# monarchdtv.net
KiCad netlist of a schematic drawn in EAGLE
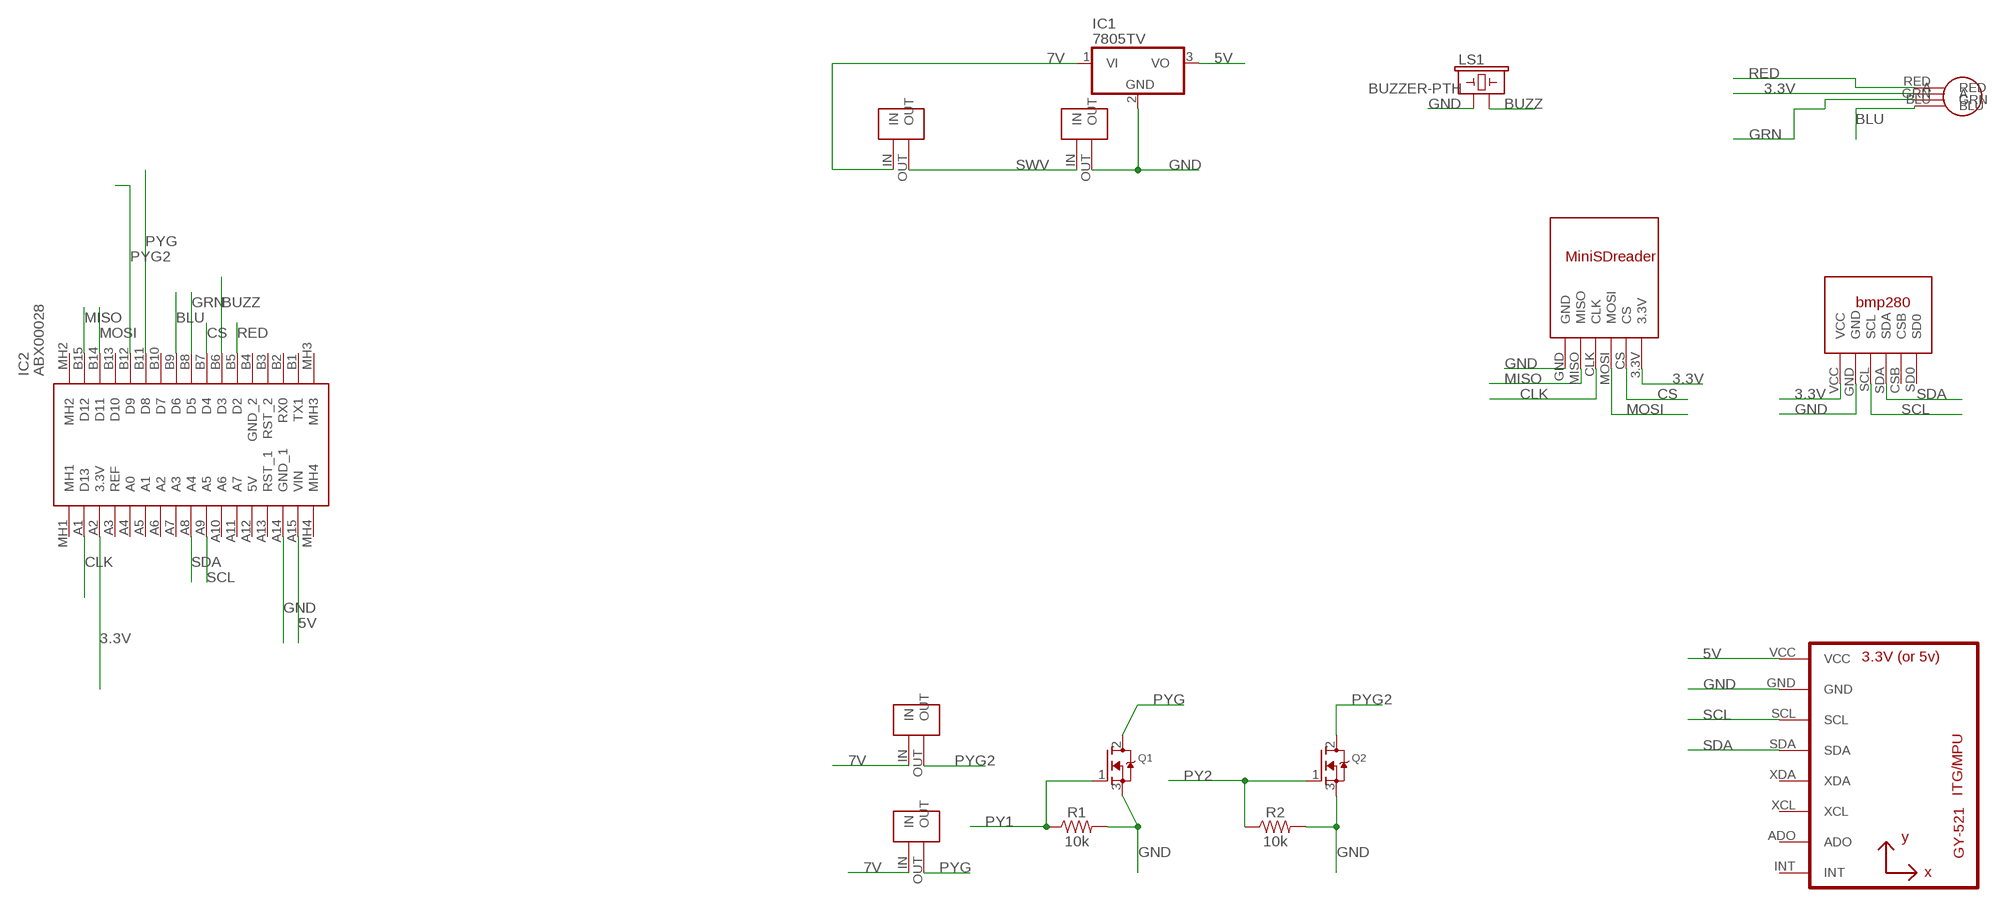
[diagram p0: schematic, sheet 1]

(export (version "E")
  (design (tool "Eeschema 10.0.6"))
  (components
    (comp (ref "IC1")
      (value "7805TV")
      (footprint "eagle-import:TO220V")
      (libsource (lib "eagle-import") (part "78TV05"))
    )
    (comp (ref "IC2")
      (value "ABX00028")
      (footprint "eagle-import:ABX00028")
      (fields (field (name "MOUSER_PART_NUMBER") "782-ABX00028"))
      (libsource (lib "eagle-import") (part "ABX00028"))
    )
    (comp (ref "LS1")
      (value "BUZZER-PTH")
      (footprint "eagle-import:BUZZER-12MM")
      (libsource (lib "eagle-import") (part "BUZZER-PTH"))
    )
    (comp (ref "Q1")
      (value "MOSFET-NGDS_TO220V")
      (footprint "eagle-import:TO220V")
      (libsource (lib "eagle-import") (part "MOSFET-NGDS_TO220V"))
    )
    (comp (ref "Q2")
      (value "MOSFET-NGDS_TO220V")
      (footprint "eagle-import:TO220V")
      (libsource (lib "eagle-import") (part "MOSFET-NGDS_TO220V"))
    )
    (comp (ref "R1")
      (value "10k")
      (footprint "eagle-import:AXIAL-0.1-KIT")
      (libsource (lib "eagle-import") (part "10KOHM-VERT_KIT-1/6W-5%"))
    )
    (comp (ref "R2")
      (value "10k")
      (footprint "eagle-import:AXIAL-0.1-KIT")
      (libsource (lib "eagle-import") (part "10KOHM-VERT_KIT-1/6W-5%"))
    )
    (comp (ref "U$2")
      (value "BMP280")
      (footprint "eagle-import:BMP280")
      (libsource (lib "eagle-import") (part "BMP280"))
    )
    (comp (ref "U$3")
      (value "MINISDREADER")
      (footprint "eagle-import:MINISDREADER")
      (libsource (lib "eagle-import") (part "MINISDREADER"))
    )
    (comp (ref "U$4")
      (value "SWITCH")
      (footprint "eagle-import:SWITCH")
      (libsource (lib "eagle-import") (part "SWITCH"))
    )
    (comp (ref "U$5")
      (value "SWITCH")
      (footprint "eagle-import:SWITCH")
      (libsource (lib "eagle-import") (part "SWITCH"))
    )
    (comp (ref "U$6")
      (value "SWITCH")
      (footprint "eagle-import:SWITCH")
      (libsource (lib "eagle-import") (part "SWITCH"))
    )
    (comp (ref "U$7")
      (value "SWITCH")
      (footprint "eagle-import:SWITCH")
      (libsource (lib "eagle-import") (part "SWITCH"))
    )
    (comp (ref "U$9")
      (value "LED")
      (footprint "eagle-import:LED")
      (libsource (lib "eagle-import") (part "LED"))
    )
    (comp (ref "U1")
      (value "GY-521MPU6050")
      (footprint "eagle-import:GY-521")
      (libsource (lib "eagle-import") (part "GY-521MPU6050"))
    )
  )
  (nets
    (net (code "1") (name "/3.3V") (class "Default")
      (node (ref "IC2") (pin "A2") (pinfunction "3.3V_A2") (pintype "bidirectional"))
      (node (ref "U$2") (pin "VCC") (pinfunction "VCC_VCC") (pintype "bidirectional"))
      (node (ref "U$3") (pin "3.3V") (pinfunction "3.3V_3.3V") (pintype "bidirectional"))
      (node (ref "U$9") (pin "A") (pinfunction "A_A") (pintype "bidirectional"))
    )
    (net (code "2") (name "/5V") (class "Default")
      (node (ref "IC1") (pin "3") (pinfunction "VO_3") (pintype "passive"))
      (node (ref "IC2") (pin "A15") (pinfunction "VIN_A15") (pintype "bidirectional"))
      (node (ref "U1") (pin "VCC") (pinfunction "VCC_VCC") (pintype "bidirectional"))
    )
    (net (code "3") (name "/7V") (class "Default")
      (node (ref "IC1") (pin "1") (pinfunction "VI_1") (pintype "input"))
      (node (ref "U$5") (pin "IN") (pinfunction "IN_IN") (pintype "bidirectional"))
      (node (ref "U$6") (pin "IN") (pinfunction "IN_IN") (pintype "bidirectional"))
      (node (ref "U$7") (pin "IN") (pinfunction "IN_IN") (pintype "bidirectional"))
    )
    (net (code "4") (name "/BLU") (class "Default")
      (node (ref "IC2") (pin "B9") (pinfunction "D6_B9") (pintype "bidirectional"))
      (node (ref "U$9") (pin "BLU") (pinfunction "BLU_BLU") (pintype "bidirectional"))
    )
    (net (code "5") (name "/BUZZ") (class "Default")
      (node (ref "IC2") (pin "B6") (pinfunction "D3_B6") (pintype "bidirectional"))
      (node (ref "LS1") (pin "-") (pinfunction "2_-") (pintype "passive"))
    )
    (net (code "6") (name "/CLK") (class "Default")
      (node (ref "IC2") (pin "A1") (pinfunction "D13_A1") (pintype "bidirectional"))
      (node (ref "U$3") (pin "CLK") (pinfunction "CLK_CLK") (pintype "bidirectional"))
    )
    (net (code "7") (name "/CS") (class "Default")
      (node (ref "IC2") (pin "B7") (pinfunction "D4_B7") (pintype "bidirectional"))
      (node (ref "U$3") (pin "CS") (pinfunction "CS_CS") (pintype "bidirectional"))
    )
    (net (code "8") (name "/GND") (class "Default")
      (node (ref "IC1") (pin "2") (pinfunction "GND_2") (pintype "passive"))
      (node (ref "IC2") (pin "A14") (pinfunction "GND_1_A14") (pintype "bidirectional"))
      (node (ref "LS1") (pin "+") (pinfunction "1_+") (pintype "passive"))
      (node (ref "Q1") (pin "3") (pinfunction "S_3") (pintype "bidirectional"))
      (node (ref "Q2") (pin "3") (pinfunction "S_3") (pintype "bidirectional"))
      (node (ref "R1") (pin "P$2") (pinfunction "2_P$2") (pintype "passive"))
      (node (ref "R2") (pin "P$2") (pinfunction "2_P$2") (pintype "passive"))
      (node (ref "U$2") (pin "GND") (pinfunction "GND_GND") (pintype "bidirectional"))
      (node (ref "U$3") (pin "GND") (pinfunction "GND_GND") (pintype "bidirectional"))
      (node (ref "U$4") (pin "OUT") (pinfunction "OUT_OUT") (pintype "bidirectional"))
      (node (ref "U1") (pin "GND") (pinfunction "GND_GND") (pintype "bidirectional"))
    )
    (net (code "9") (name "/GRN") (class "Default")
      (node (ref "IC2") (pin "B8") (pinfunction "D5_B8") (pintype "bidirectional"))
      (node (ref "U$9") (pin "GRN") (pinfunction "GRN_GRN") (pintype "bidirectional"))
    )
    (net (code "10") (name "/MISO") (class "Default")
      (node (ref "IC2") (pin "B15") (pinfunction "D12_B15") (pintype "bidirectional"))
      (node (ref "U$3") (pin "MISO") (pinfunction "MISO_MISO") (pintype "bidirectional"))
    )
    (net (code "11") (name "/MOSI") (class "Default")
      (node (ref "IC2") (pin "B14") (pinfunction "D11_B14") (pintype "bidirectional"))
      (node (ref "U$3") (pin "MOSI") (pinfunction "MOSI_MOSI") (pintype "bidirectional"))
    )
    (net (code "12") (name "/PY1") (class "Default")
      (node (ref "Q1") (pin "1") (pinfunction "G_1") (pintype "bidirectional"))
      (node (ref "R1") (pin "P$1") (pinfunction "1_P$1") (pintype "passive"))
    )
    (net (code "13") (name "/PY2") (class "Default")
      (node (ref "Q2") (pin "1") (pinfunction "G_1") (pintype "bidirectional"))
      (node (ref "R2") (pin "P$1") (pinfunction "1_P$1") (pintype "passive"))
    )
    (net (code "14") (name "/PYG") (class "Default")
      (node (ref "IC2") (pin "B11") (pinfunction "D8_B11") (pintype "bidirectional"))
      (node (ref "Q1") (pin "2") (pinfunction "D_2") (pintype "bidirectional"))
      (node (ref "U$6") (pin "OUT") (pinfunction "OUT_OUT") (pintype "bidirectional"))
    )
    (net (code "15") (name "/PYG2") (class "Default")
      (node (ref "IC2") (pin "B12") (pinfunction "D9_B12") (pintype "bidirectional"))
      (node (ref "Q2") (pin "2") (pinfunction "D_2") (pintype "bidirectional"))
      (node (ref "U$5") (pin "OUT") (pinfunction "OUT_OUT") (pintype "bidirectional"))
    )
    (net (code "16") (name "/RED") (class "Default")
      (node (ref "IC2") (pin "B5") (pinfunction "D2_B5") (pintype "bidirectional"))
      (node (ref "U$9") (pin "RED") (pinfunction "RED_RED") (pintype "bidirectional"))
    )
    (net (code "17") (name "/SCL") (class "Default")
      (node (ref "IC2") (pin "A9") (pinfunction "A5_A9") (pintype "bidirectional"))
      (node (ref "U$2") (pin "SCL") (pinfunction "SCL_SCL") (pintype "bidirectional"))
      (node (ref "U1") (pin "SCL") (pinfunction "SCL_SCL") (pintype "bidirectional"))
    )
    (net (code "18") (name "/SDA") (class "Default")
      (node (ref "IC2") (pin "A8") (pinfunction "A4_A8") (pintype "bidirectional"))
      (node (ref "U$2") (pin "SDA") (pinfunction "SDA_SDA") (pintype "bidirectional"))
      (node (ref "U1") (pin "SDA") (pinfunction "SDA_SDA") (pintype "bidirectional"))
    )
    (net (code "19") (name "/SWV") (class "Default")
      (node (ref "U$4") (pin "IN") (pinfunction "IN_IN") (pintype "bidirectional"))
      (node (ref "U$7") (pin "OUT") (pinfunction "OUT_OUT") (pintype "bidirectional"))
    )
    (net (code "20") (name "unconnected-(IC2-5V-PadA12)") (class "Default")
      (node (ref "IC2") (pin "A12") (pinfunction "5V_A12") (pintype "bidirectional"))
    )
    (net (code "21") (name "unconnected-(IC2-A0-PadA4)") (class "Default")
      (node (ref "IC2") (pin "A4") (pinfunction "A0_A4") (pintype "bidirectional"))
    )
    (net (code "22") (name "unconnected-(IC2-A1-PadA5)") (class "Default")
      (node (ref "IC2") (pin "A5") (pinfunction "A1_A5") (pintype "bidirectional"))
    )
    (net (code "23") (name "unconnected-(IC2-A2-PadA6)") (class "Default")
      (node (ref "IC2") (pin "A6") (pinfunction "A2_A6") (pintype "bidirectional"))
    )
    (net (code "24") (name "unconnected-(IC2-A3-PadA7)") (class "Default")
      (node (ref "IC2") (pin "A7") (pinfunction "A3_A7") (pintype "bidirectional"))
    )
    (net (code "25") (name "unconnected-(IC2-A6-PadA10)") (class "Default")
      (node (ref "IC2") (pin "A10") (pinfunction "A6_A10") (pintype "bidirectional"))
    )
    (net (code "26") (name "unconnected-(IC2-A7-PadA11)") (class "Default")
      (node (ref "IC2") (pin "A11") (pinfunction "A7_A11") (pintype "bidirectional"))
    )
    (net (code "27") (name "unconnected-(IC2-D7-PadB10)") (class "Default")
      (node (ref "IC2") (pin "B10") (pinfunction "D7_B10") (pintype "bidirectional"))
    )
    (net (code "28") (name "unconnected-(IC2-D10-PadB13)") (class "Default")
      (node (ref "IC2") (pin "B13") (pinfunction "D10_B13") (pintype "bidirectional"))
    )
    (net (code "29") (name "unconnected-(IC2-GND_2-PadB4)") (class "Default")
      (node (ref "IC2") (pin "B4") (pinfunction "GND_2_B4") (pintype "bidirectional"))
    )
    (net (code "30") (name "unconnected-(IC2-PadMH1)") (class "Default")
      (node (ref "IC2") (pin "MH1") (pinfunction "MH1_MH1") (pintype "bidirectional"))
    )
    (net (code "31") (name "unconnected-(IC2-PadMH2)") (class "Default")
      (node (ref "IC2") (pin "MH2") (pinfunction "MH2_MH2") (pintype "bidirectional"))
    )
    (net (code "32") (name "unconnected-(IC2-PadMH3)") (class "Default")
      (node (ref "IC2") (pin "MH3") (pinfunction "MH3_MH3") (pintype "bidirectional"))
    )
    (net (code "33") (name "unconnected-(IC2-PadMH4)") (class "Default")
      (node (ref "IC2") (pin "MH4") (pinfunction "MH4_MH4") (pintype "bidirectional"))
    )
    (net (code "34") (name "unconnected-(IC2-REF-PadA3)") (class "Default")
      (node (ref "IC2") (pin "A3") (pinfunction "REF_A3") (pintype "bidirectional"))
    )
    (net (code "35") (name "unconnected-(IC2-RST_1-PadA13)") (class "Default")
      (node (ref "IC2") (pin "A13") (pinfunction "RST_1_A13") (pintype "bidirectional"))
    )
    (net (code "36") (name "unconnected-(IC2-RST_2-PadB3)") (class "Default")
      (node (ref "IC2") (pin "B3") (pinfunction "RST_2_B3") (pintype "bidirectional"))
    )
    (net (code "37") (name "unconnected-(IC2-RX0-PadB2)") (class "Default")
      (node (ref "IC2") (pin "B2") (pinfunction "RX0_B2") (pintype "bidirectional"))
    )
    (net (code "38") (name "unconnected-(IC2-TX1-PadB1)") (class "Default")
      (node (ref "IC2") (pin "B1") (pinfunction "TX1_B1") (pintype "bidirectional"))
    )
    (net (code "39") (name "unconnected-(U$2-PadCSB)") (class "Default")
      (node (ref "U$2") (pin "CSB") (pinfunction "CSB_CSB") (pintype "bidirectional"))
    )
    (net (code "40") (name "unconnected-(U$2-PadSD0)") (class "Default")
      (node (ref "U$2") (pin "SD0") (pinfunction "SD0_SD0") (pintype "bidirectional"))
    )
    (net (code "41") (name "unconnected-(U1-PadADO)") (class "Default")
      (node (ref "U1") (pin "ADO") (pinfunction "ADO_ADO") (pintype "bidirectional"))
    )
    (net (code "42") (name "unconnected-(U1-PadINT)") (class "Default")
      (node (ref "U1") (pin "INT") (pinfunction "INT_INT") (pintype "bidirectional"))
    )
    (net (code "43") (name "unconnected-(U1-PadXCL)") (class "Default")
      (node (ref "U1") (pin "XCL") (pinfunction "XCL_XCL") (pintype "bidirectional"))
    )
    (net (code "44") (name "unconnected-(U1-PadXDA)") (class "Default")
      (node (ref "U1") (pin "XDA") (pinfunction "XDA_XDA") (pintype "bidirectional"))
    )
  )
)
